# 03_MCU_ESP32_Interface.net
KiCad netlist of a schematic drawn in Altium Designer
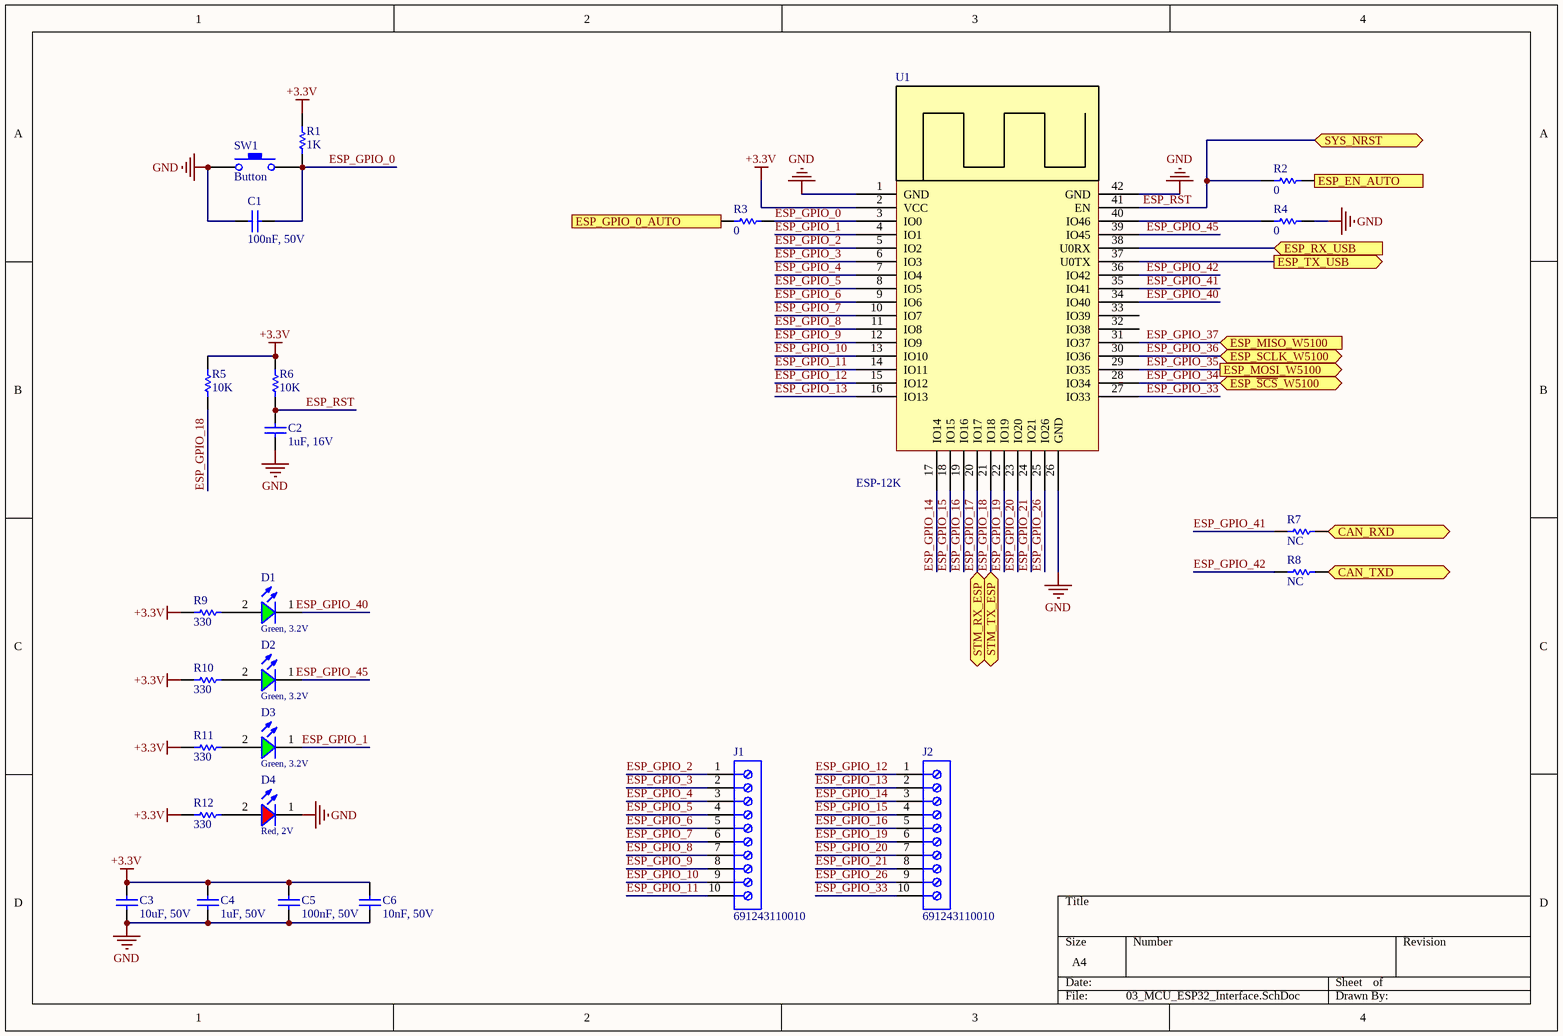
[diagram p0: 03_MCU_ESP32_Interface.SchDoc]

(export (version "E")
  (design (tool "Eeschema 10.0.6"))
  (components
    (comp (ref "C1")
      (value "100nF, 50V")
      (footprint "WCAP-CSGP_0603_H=0.8mm_Reflow")
      (description "WCAP-CSGP Multilayer Ceramic Chip Capacitor, General Purpose, size 0603, X7R, 100nF, 50V")
      (fields
        (field (name "MANUFACTURER PART NUMBER") "885012206095")
        (field (name "MANUFACTURER") "Wurth Elektronik")
      )
      (libsource (lib "Altium_WCAP-CSGP (rev20a)") (part "885012206095"))
    )
    (comp (ref "C2")
      (value "1uF, 16V")
      (footprint "WCAP-CSGP_0603_H=0.8mm_Reflow")
      (description "WCAP-CSGP Multilayer Ceramic Chip Capacitor, General Purpose, size 0603, X5R, 1uF, 16V")
      (fields
        (field (name "MANUFACTURER PART NUMBER") "885012106017")
        (field (name "MANUFACTURER") "Wurth Elektronik")
      )
      (libsource (lib "Altium_WCAP-CSGP (rev20a)") (part "885012106017"))
    )
    (comp (ref "C3")
      (value "10uF, 50V")
      (footprint "WCAP-CSGP_0603_H=0.8mm_Reflow")
      (description "WCAP-CSGP Multilayer Ceramic Chip Capacitor, General Purpose, size 0603, X7R, 100nF, 50V")
      (fields
        (field (name "MANUFACTURER PART NUMBER") "885012206095")
        (field (name "MANUFACTURER") "Wurth Elektronik")
      )
      (libsource (lib "Altium_WCAP-CSGP (rev20a)") (part "885012206095"))
    )
    (comp (ref "C4")
      (value "1uF, 50V")
      (footprint "WCAP-CSGP_0603_H=0.8mm_Reflow")
      (description "WCAP-CSGP Multilayer Ceramic Chip Capacitor, General Purpose, size 0603, X7R, 100nF, 50V")
      (fields
        (field (name "MANUFACTURER PART NUMBER") "885012206095")
        (field (name "MANUFACTURER") "Wurth Elektronik")
      )
      (libsource (lib "Altium_WCAP-CSGP (rev20a)") (part "885012206095"))
    )
    (comp (ref "C5")
      (value "100nF, 50V")
      (footprint "WCAP-CSGP_0603_H=0.8mm_Reflow")
      (description "WCAP-CSGP Multilayer Ceramic Chip Capacitor, General Purpose, size 0603, X7R, 100nF, 50V")
      (fields
        (field (name "MANUFACTURER PART NUMBER") "885012206095")
        (field (name "MANUFACTURER") "Wurth Elektronik")
      )
      (libsource (lib "Altium_WCAP-CSGP (rev20a)") (part "885012206095"))
    )
    (comp (ref "C6")
      (value "10nF, 50V")
      (footprint "WCAP-CSGP_0603_H=0.8mm_Reflow")
      (description "WCAP-CSGP Multilayer Ceramic Chip Capacitor, General Purpose, size 0603, X7R, 10nF, 50V")
      (fields
        (field (name "MANUFACTURER PART NUMBER") "885012206089")
        (field (name "MANUFACTURER") "Wurth Elektronik")
      )
      (libsource (lib "Altium_WCAP-CSGP (rev20a)") (part "885012206089"))
    )
    (comp (ref "D1")
      (value "Green, 3.2V")
      (footprint "WL-SMCW_0603_H=0.7mm")
      (description "WL-SMCW SMT Mono-color Chip LED Waterclear, size 0603, Green, 3.2V, 140deg")
      (fields (field (name "PART NUMBER") "150060GS75000") (field (name "PUBLISHER") "Wurth Elektronik"))
      (libsource (lib "Altium_WL-SMCW (rev20a)") (part "150060GS75000"))
    )
    (comp (ref "D2")
      (value "Green, 3.2V")
      (footprint "WL-SMCW_0603_H=0.7mm")
      (description "WL-SMCW SMT Mono-color Chip LED Waterclear, size 0603, Green, 3.2V, 140deg")
      (fields (field (name "PART NUMBER") "150060GS75000") (field (name "PUBLISHER") "Wurth Elektronik"))
      (libsource (lib "Altium_WL-SMCW (rev20a)") (part "150060GS75000"))
    )
    (comp (ref "D3")
      (value "Green, 3.2V")
      (footprint "WL-SMCW_0603_H=0.7mm")
      (description "WL-SMCW SMT Mono-color Chip LED Waterclear, size 0603, Green, 3.2V, 140deg")
      (fields (field (name "PART NUMBER") "150060GS75000") (field (name "PUBLISHER") "Wurth Elektronik"))
      (libsource (lib "Altium_WL-SMCW (rev20a)") (part "150060GS75000"))
    )
    (comp (ref "D4")
      (value "Red, 2V")
      (footprint "WL-SMCW_0603_H=0.7mm")
      (description "WL-SMCW SMT Mono-color Chip LED Waterclear, size 0603, Red, 2V, 140deg")
      (fields (field (name "PART NUMBER") "150060RS75000") (field (name "PUBLISHER") "Wurth Elektronik"))
      (libsource (lib "Altium_WL-SMCW (rev20a)") (part "150060RS75000"))
    )
    (comp (ref "J1")
      (value "691243110010")
      (footprint "691243110010")
      (description "WR-TBL Serie 2431 Horizontal Cable Entry, Rising Cage Clamp, pitch 3.5mm, 10p")
      (fields (field (name "PUBLISHER") "Wurth Elektronik"))
      (libsource (lib "691322310002.") (part "691243110010"))
    )
    (comp (ref "J2")
      (value "691243110010")
      (footprint "691243110010")
      (description "WR-TBL Serie 2431 Horizontal Cable Entry, Rising Cage Clamp, pitch 3.5mm, 10p")
      (fields (field (name "PUBLISHER") "Wurth Elektronik"))
      (libsource (lib "691322310002.") (part "691243110010"))
    )
    (comp (ref "R1")
      (value "1K")
      (footprint "RES-SM-0603")
      (description "Resistor")
      (fields (field (name "Comment") "RESISTOR SMD"))
      (libsource (lib "PIF_Library") (part "RESISTOR SMD"))
    )
    (comp (ref "R2")
      (value "0")
      (footprint "RES-SM-0603")
      (description "Resistor")
      (fields (field (name "Comment") "RESISTOR SMD"))
      (libsource (lib "PIF_Library") (part "RESISTOR SMD"))
    )
    (comp (ref "R3")
      (value "0")
      (footprint "RES-SM-0603")
      (description "Resistor")
      (fields (field (name "Comment") "RESISTOR SMD"))
      (libsource (lib "PIF_Library") (part "RESISTOR SMD"))
    )
    (comp (ref "R4")
      (value "0")
      (footprint "RES-SM-0603")
      (description "Resistor")
      (fields (field (name "Comment") "RESISTOR SMD"))
      (libsource (lib "PIF_Library") (part "RESISTOR SMD"))
    )
    (comp (ref "R5")
      (value "10K")
      (footprint "RES-SM-0603")
      (description "Resistor")
      (fields (field (name "Comment") "RESISTOR SMD"))
      (libsource (lib "PIF_Library") (part "RESISTOR SMD"))
    )
    (comp (ref "R6")
      (value "10K")
      (footprint "RES-SM-0603")
      (description "Resistor")
      (fields (field (name "Comment") "RESISTOR SMD"))
      (libsource (lib "PIF_Library") (part "RESISTOR SMD"))
    )
    (comp (ref "R7")
      (value "NC")
      (footprint "RES-SM-0603")
      (description "Resistor")
      (fields (field (name "Comment") "RESISTOR SMD"))
      (libsource (lib "PIF_Library") (part "RESISTOR SMD"))
    )
    (comp (ref "R8")
      (value "NC")
      (footprint "RES-SM-0603")
      (description "Resistor")
      (fields (field (name "Comment") "RESISTOR SMD"))
      (libsource (lib "PIF_Library") (part "RESISTOR SMD"))
    )
    (comp (ref "R9")
      (value "330")
      (footprint "RES-SM-0603")
      (description "Resistor")
      (fields (field (name "Comment") "RESISTOR SMD"))
      (libsource (lib "PIF_Library") (part "RESISTOR SMD"))
    )
    (comp (ref "R10")
      (value "330")
      (footprint "RES-SM-0603")
      (description "Resistor")
      (fields (field (name "Comment") "RESISTOR SMD"))
      (libsource (lib "PIF_Library") (part "RESISTOR SMD"))
    )
    (comp (ref "R11")
      (value "330")
      (footprint "RES-SM-0603")
      (description "Resistor")
      (fields (field (name "Comment") "RESISTOR SMD"))
      (libsource (lib "PIF_Library") (part "RESISTOR SMD"))
    )
    (comp (ref "R12")
      (value "330")
      (footprint "RES-SM-0603")
      (description "Resistor")
      (fields (field (name "Comment") "RESISTOR SMD"))
      (libsource (lib "PIF_Library") (part "RESISTOR SMD"))
    )
    (comp (ref "SW1")
      (value "Button")
      (footprint "Button 4-pin SMD")
      (libsource (lib "MiclsLib") (part "Button"))
    )
    (comp (ref "U1")
      (value "ESP-12K")
      (footprint "CAC-150P3100X1800-41N")
      (description "ESP32-S2")
      (libsource (lib "MiclsLib") (part "ESP-12K"))
    )
  )
  (nets
    (net (code "1") (name "+3.3V") (class "Default")
      (node (ref "C3") (pin "2") (pinfunction "2_2") (pintype "passive"))
      (node (ref "C4") (pin "2") (pinfunction "2_2") (pintype "passive"))
      (node (ref "C5") (pin "2") (pinfunction "2_2") (pintype "passive"))
      (node (ref "C6") (pin "2") (pinfunction "2_2") (pintype "passive"))
      (node (ref "R1") (pin "2") (pinfunction "2_2") (pintype "passive"))
      (node (ref "R10") (pin "2") (pinfunction "2_2") (pintype "passive"))
      (node (ref "R11") (pin "2") (pinfunction "2_2") (pintype "passive"))
      (node (ref "R12") (pin "2") (pinfunction "2_2") (pintype "passive"))
      (node (ref "R5") (pin "2") (pinfunction "2_2") (pintype "passive"))
      (node (ref "R6") (pin "2") (pinfunction "2_2") (pintype "passive"))
      (node (ref "R9") (pin "2") (pinfunction "2_2") (pintype "passive"))
      (node (ref "U1") (pin "2") (pinfunction "VCC_2") (pintype "passive"))
    )
    (net (code "2") (name "/CAN_RXD") (class "Default")
      (node (ref "R7") (pin "2") (pinfunction "2_2") (pintype "passive"))
    )
    (net (code "3") (name "/CAN_TXD") (class "Default")
      (node (ref "R8") (pin "2") (pinfunction "2_2") (pintype "passive"))
    )
    (net (code "4") (name "/ESP_EN_AUTO") (class "Default")
      (node (ref "R2") (pin "2") (pinfunction "2_2") (pintype "passive"))
    )
    (net (code "5") (name "/ESP_GPIO_0") (class "Default")
      (node (ref "C1") (pin "2") (pinfunction "2_2") (pintype "passive"))
      (node (ref "R1") (pin "1") (pinfunction "1_1") (pintype "passive"))
      (node (ref "R3") (pin "1") (pinfunction "1_1") (pintype "passive"))
      (node (ref "SW1") (pin "2") (pinfunction "8_2") (pintype "passive"))
      (node (ref "U1") (pin "3") (pinfunction "IO0_3") (pintype "passive"))
    )
    (net (code "6") (name "/ESP_GPIO_0_AUTO") (class "Default")
      (node (ref "R3") (pin "2") (pinfunction "2_2") (pintype "passive"))
    )
    (net (code "7") (name "/ESP_GPIO_1") (class "Default")
      (node (ref "D3") (pin "1") (pinfunction "K_1") (pintype "passive"))
      (node (ref "U1") (pin "4") (pinfunction "IO1_4") (pintype "passive"))
    )
    (net (code "8") (name "/ESP_GPIO_2") (class "Default")
      (node (ref "J1") (pin "1") (pinfunction "1_1") (pintype "passive"))
      (node (ref "U1") (pin "5") (pinfunction "IO2_5") (pintype "passive"))
    )
    (net (code "9") (name "/ESP_GPIO_3") (class "Default")
      (node (ref "J1") (pin "2") (pinfunction "2_2") (pintype "passive"))
      (node (ref "U1") (pin "6") (pinfunction "IO3_6") (pintype "passive"))
    )
    (net (code "10") (name "/ESP_GPIO_4") (class "Default")
      (node (ref "J1") (pin "3") (pinfunction "3_3") (pintype "passive"))
      (node (ref "U1") (pin "7") (pinfunction "IO4_7") (pintype "passive"))
    )
    (net (code "11") (name "/ESP_GPIO_5") (class "Default")
      (node (ref "J1") (pin "4") (pinfunction "4_4") (pintype "passive"))
      (node (ref "U1") (pin "8") (pinfunction "IO5_8") (pintype "passive"))
    )
    (net (code "12") (name "/ESP_GPIO_6") (class "Default")
      (node (ref "J1") (pin "5") (pinfunction "5_5") (pintype "passive"))
      (node (ref "U1") (pin "9") (pinfunction "IO6_9") (pintype "passive"))
    )
    (net (code "13") (name "/ESP_GPIO_7") (class "Default")
      (node (ref "J1") (pin "6") (pinfunction "6_6") (pintype "passive"))
      (node (ref "U1") (pin "10") (pinfunction "IO7_10") (pintype "passive"))
    )
    (net (code "14") (name "/ESP_GPIO_8") (class "Default")
      (node (ref "J1") (pin "7") (pinfunction "7_7") (pintype "passive"))
      (node (ref "U1") (pin "11") (pinfunction "IO8_11") (pintype "passive"))
    )
    (net (code "15") (name "/ESP_GPIO_9") (class "Default")
      (node (ref "J1") (pin "8") (pinfunction "8_8") (pintype "passive"))
      (node (ref "U1") (pin "12") (pinfunction "IO9_12") (pintype "passive"))
    )
    (net (code "16") (name "/ESP_GPIO_10") (class "Default")
      (node (ref "J1") (pin "9") (pinfunction "9_9") (pintype "passive"))
      (node (ref "U1") (pin "13") (pinfunction "IO10_13") (pintype "passive"))
    )
    (net (code "17") (name "/ESP_GPIO_11") (class "Default")
      (node (ref "J1") (pin "10") (pinfunction "10_10") (pintype "passive"))
      (node (ref "U1") (pin "14") (pinfunction "IO11_14") (pintype "passive"))
    )
    (net (code "18") (name "/ESP_GPIO_12") (class "Default")
      (node (ref "J2") (pin "1") (pinfunction "1_1") (pintype "passive"))
      (node (ref "U1") (pin "15") (pinfunction "IO12_15") (pintype "passive"))
    )
    (net (code "19") (name "/ESP_GPIO_13") (class "Default")
      (node (ref "J2") (pin "2") (pinfunction "2_2") (pintype "passive"))
      (node (ref "U1") (pin "16") (pinfunction "IO13_16") (pintype "passive"))
    )
    (net (code "20") (name "/ESP_GPIO_14") (class "Default")
      (node (ref "J2") (pin "3") (pinfunction "3_3") (pintype "passive"))
      (node (ref "U1") (pin "17") (pinfunction "IO14_17") (pintype "passive"))
    )
    (net (code "21") (name "/ESP_GPIO_15") (class "Default")
      (node (ref "J2") (pin "4") (pinfunction "4_4") (pintype "passive"))
      (node (ref "U1") (pin "18") (pinfunction "IO15_18") (pintype "passive"))
    )
    (net (code "22") (name "/ESP_GPIO_16") (class "Default")
      (node (ref "J2") (pin "5") (pinfunction "5_5") (pintype "passive"))
      (node (ref "U1") (pin "19") (pinfunction "IO16_19") (pintype "passive"))
    )
    (net (code "23") (name "/ESP_GPIO_17") (class "Default")
      (node (ref "U1") (pin "20") (pinfunction "IO17_20") (pintype "passive"))
    )
    (net (code "24") (name "/ESP_GPIO_18") (class "Default")
      (node (ref "R5") (pin "1") (pinfunction "1_1") (pintype "passive"))
      (node (ref "U1") (pin "21") (pinfunction "IO18_21") (pintype "passive"))
    )
    (net (code "25") (name "/ESP_GPIO_19") (class "Default")
      (node (ref "J2") (pin "6") (pinfunction "6_6") (pintype "passive"))
      (node (ref "U1") (pin "22") (pinfunction "IO19_22") (pintype "passive"))
    )
    (net (code "26") (name "/ESP_GPIO_20") (class "Default")
      (node (ref "J2") (pin "7") (pinfunction "7_7") (pintype "passive"))
      (node (ref "U1") (pin "23") (pinfunction "IO20_23") (pintype "passive"))
    )
    (net (code "27") (name "/ESP_GPIO_21") (class "Default")
      (node (ref "J2") (pin "8") (pinfunction "8_8") (pintype "passive"))
      (node (ref "U1") (pin "24") (pinfunction "IO21_24") (pintype "passive"))
    )
    (net (code "28") (name "/ESP_GPIO_26") (class "Default")
      (node (ref "J2") (pin "9") (pinfunction "9_9") (pintype "passive"))
      (node (ref "U1") (pin "25") (pinfunction "IO26_25") (pintype "passive"))
    )
    (net (code "29") (name "/ESP_GPIO_33") (class "Default")
      (node (ref "J2") (pin "10") (pinfunction "10_10") (pintype "passive"))
      (node (ref "U1") (pin "27") (pinfunction "IO33_27") (pintype "passive"))
    )
    (net (code "30") (name "/ESP_GPIO_34") (class "Default")
      (node (ref "U1") (pin "28") (pinfunction "IO34_28") (pintype "passive"))
    )
    (net (code "31") (name "/ESP_GPIO_35") (class "Default")
      (node (ref "U1") (pin "29") (pinfunction "IO35_29") (pintype "passive"))
    )
    (net (code "32") (name "/ESP_GPIO_36") (class "Default")
      (node (ref "U1") (pin "30") (pinfunction "IO36_30") (pintype "passive"))
    )
    (net (code "33") (name "/ESP_GPIO_37") (class "Default")
      (node (ref "U1") (pin "31") (pinfunction "IO37_31") (pintype "passive"))
    )
    (net (code "34") (name "/ESP_GPIO_40") (class "Default")
      (node (ref "D1") (pin "1") (pinfunction "K_1") (pintype "passive"))
      (node (ref "U1") (pin "34") (pinfunction "IO40_34") (pintype "passive"))
    )
    (net (code "35") (name "/ESP_GPIO_41") (class "Default")
      (node (ref "R7") (pin "1") (pinfunction "1_1") (pintype "passive"))
      (node (ref "U1") (pin "35") (pinfunction "IO41_35") (pintype "passive"))
    )
    (net (code "36") (name "/ESP_GPIO_42") (class "Default")
      (node (ref "R8") (pin "1") (pinfunction "1_1") (pintype "passive"))
      (node (ref "U1") (pin "36") (pinfunction "IO42_36") (pintype "passive"))
    )
    (net (code "37") (name "/ESP_GPIO_45") (class "Default")
      (node (ref "D2") (pin "1") (pinfunction "K_1") (pintype "passive"))
      (node (ref "U1") (pin "39") (pinfunction "IO45_39") (pintype "passive"))
    )
    (net (code "38") (name "/ESP_RST") (class "Default")
      (node (ref "C2") (pin "2") (pinfunction "2_2") (pintype "passive"))
      (node (ref "R2") (pin "1") (pinfunction "1_1") (pintype "passive"))
      (node (ref "R6") (pin "1") (pinfunction "1_1") (pintype "passive"))
      (node (ref "U1") (pin "41") (pinfunction "EN_41") (pintype "passive"))
    )
    (net (code "39") (name "/ESP_RX_USB") (class "Default")
      (node (ref "U1") (pin "38") (pinfunction "U0RX_38") (pintype "passive"))
    )
    (net (code "40") (name "/ESP_TX_USB") (class "Default")
      (node (ref "U1") (pin "37") (pinfunction "U0TX_37") (pintype "passive"))
    )
    (net (code "41") (name "GND") (class "Default")
      (node (ref "C1") (pin "1") (pinfunction "1_1") (pintype "passive"))
      (node (ref "C2") (pin "1") (pinfunction "1_1") (pintype "passive"))
      (node (ref "C3") (pin "1") (pinfunction "1_1") (pintype "passive"))
      (node (ref "C4") (pin "1") (pinfunction "1_1") (pintype "passive"))
      (node (ref "C5") (pin "1") (pinfunction "1_1") (pintype "passive"))
      (node (ref "C6") (pin "1") (pinfunction "1_1") (pintype "passive"))
      (node (ref "D4") (pin "1") (pinfunction "K_1") (pintype "passive"))
      (node (ref "R4") (pin "2") (pinfunction "2_2") (pintype "passive"))
      (node (ref "SW1") (pin "1") (pinfunction "7_1") (pintype "passive"))
      (node (ref "U1") (pin "1") (pinfunction "GND_1") (pintype "passive"))
      (node (ref "U1") (pin "26") (pinfunction "GND_26") (pintype "passive"))
      (node (ref "U1") (pin "42") (pinfunction "GND_42") (pintype "passive"))
    )
    (net (code "42") (name "Net-(D1-A)") (class "Default")
      (node (ref "D1") (pin "2") (pinfunction "A_2") (pintype "passive"))
      (node (ref "R9") (pin "1") (pinfunction "1_1") (pintype "passive"))
    )
    (net (code "43") (name "Net-(D2-A)") (class "Default")
      (node (ref "D2") (pin "2") (pinfunction "A_2") (pintype "passive"))
      (node (ref "R10") (pin "1") (pinfunction "1_1") (pintype "passive"))
    )
    (net (code "44") (name "Net-(D3-A)") (class "Default")
      (node (ref "D3") (pin "2") (pinfunction "A_2") (pintype "passive"))
      (node (ref "R11") (pin "1") (pinfunction "1_1") (pintype "passive"))
    )
    (net (code "45") (name "Net-(D4-A)") (class "Default")
      (node (ref "D4") (pin "2") (pinfunction "A_2") (pintype "passive"))
      (node (ref "R12") (pin "1") (pinfunction "1_1") (pintype "passive"))
    )
    (net (code "46") (name "Net-(U1-IO46)") (class "Default")
      (node (ref "R4") (pin "1") (pinfunction "1_1") (pintype "passive"))
      (node (ref "U1") (pin "40") (pinfunction "IO46_40") (pintype "passive"))
    )
    (net (code "47") (name "unconnected-(U1-IO38-Pad32)") (class "Default")
      (node (ref "U1") (pin "32") (pinfunction "IO38_32") (pintype "passive"))
    )
    (net (code "48") (name "unconnected-(U1-IO39-Pad33)") (class "Default")
      (node (ref "U1") (pin "33") (pinfunction "IO39_33") (pintype "passive"))
    )
  )
)
